# BSPD.net
KiCad netlist of a schematic drawn in EAGLE
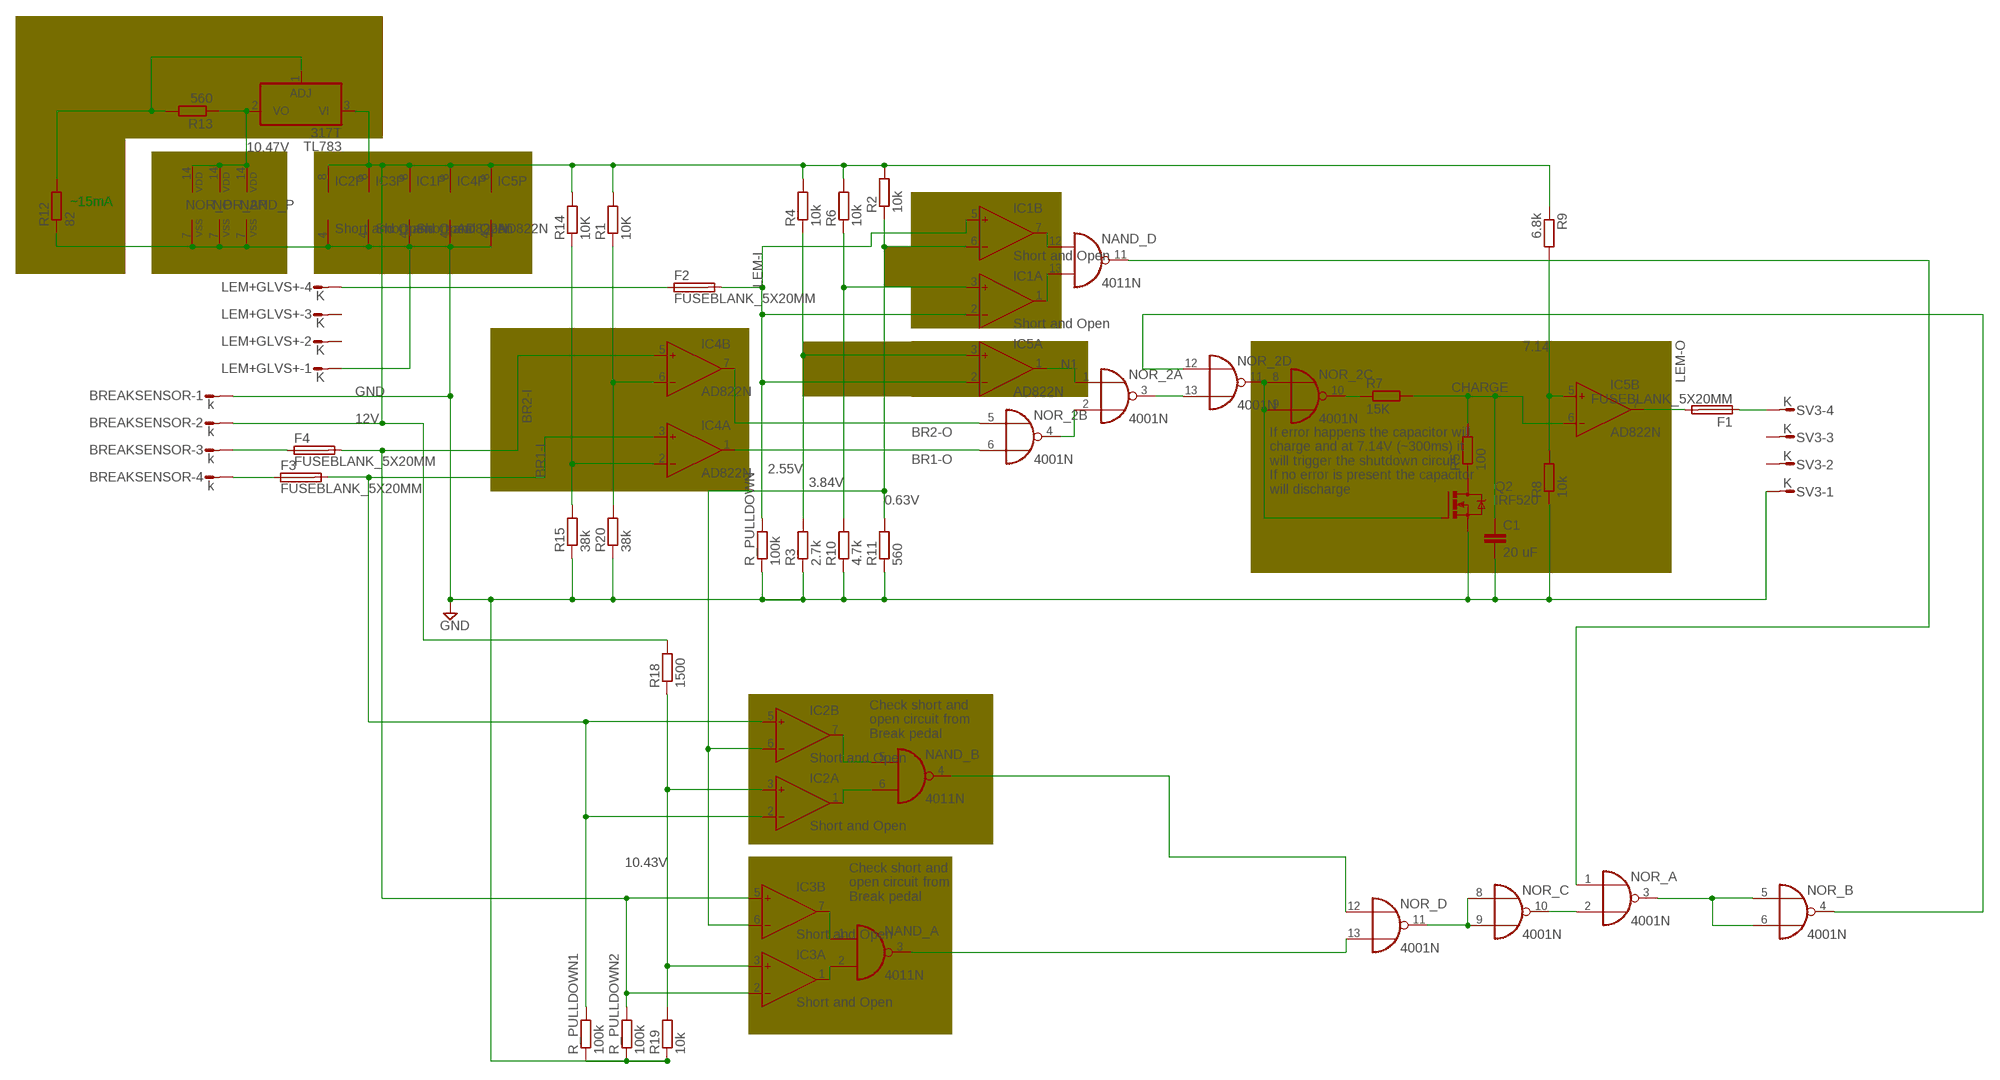
[diagram p0: schematic, sheet 1]

(export (version "E")
  (design (tool "Eeschema 10.0.6"))
  (components
    (comp (ref "BREAKSENSOR")
      (value "k")
      (footprint "eagle-import:L04P")
      (libsource (lib "eagle-import") (part "L04P"))
    )
    (comp (ref "C1")
      (value "20 uF")
      (footprint "eagle-import:C2.5-5")
      (libsource (lib "eagle-import") (part "C2.5/5"))
    )
    (comp (ref "F1")
      (value "FUSEBLANK_5X20MM")
      (footprint "eagle-import:FUSE_HOLDER_5X20MM")
      (libsource (lib "eagle-import") (part "FUSEBLANK_5X20MM"))
    )
    (comp (ref "F2")
      (value "FUSEBLANK_5X20MM")
      (footprint "eagle-import:FUSE_HOLDER_5X20MM")
      (libsource (lib "eagle-import") (part "FUSEBLANK_5X20MM"))
    )
    (comp (ref "F3")
      (value "FUSEBLANK_5X20MM")
      (footprint "eagle-import:FUSE_HOLDER_5X20MM")
      (libsource (lib "eagle-import") (part "FUSEBLANK_5X20MM"))
    )
    (comp (ref "F4")
      (value "FUSEBLANK_5X20MM")
      (footprint "eagle-import:FUSE_HOLDER_5X20MM")
      (libsource (lib "eagle-import") (part "FUSEBLANK_5X20MM"))
    )
    (comp (ref "IC1")
      (value "Short and Open")
      (footprint "eagle-import:DIL08")
      (libsource (lib "eagle-import") (part "AD822N"))
    )
    (comp (ref "IC2")
      (value "Short and Open")
      (footprint "eagle-import:DIL08")
      (libsource (lib "eagle-import") (part "AD822N"))
    )
    (comp (ref "IC3")
      (value "Short and Open")
      (footprint "eagle-import:DIL08")
      (libsource (lib "eagle-import") (part "AD822N"))
    )
    (comp (ref "IC4")
      (value "AD822N")
      (footprint "eagle-import:DIL08")
      (libsource (lib "eagle-import") (part "AD822N"))
    )
    (comp (ref "IC5")
      (value "AD822N")
      (footprint "eagle-import:DIL08")
      (libsource (lib "eagle-import") (part "AD822N"))
    )
    (comp (ref "LEM+GLVS+")
      (value "K")
      (footprint "eagle-import:L04P")
      (libsource (lib "eagle-import") (part "L04P"))
    )
    (comp (ref "NAND_")
      (value "4011N")
      (footprint "eagle-import:DIL14")
      (libsource (lib "eagle-import") (part "4011N"))
    )
    (comp (ref "NOR_")
      (value "4001N")
      (footprint "eagle-import:DIL14")
      (fields (field (name "SPICEPREFIX") "J"))
      (libsource (lib "eagle-import") (part "4001N"))
    )
    (comp (ref "NOR_2")
      (value "4001N")
      (footprint "eagle-import:DIL14")
      (fields (field (name "SPICEPREFIX") "J"))
      (libsource (lib "eagle-import") (part "4001N"))
    )
    (comp (ref "Q2")
      (value "IRF520")
      (footprint "eagle-import:TO220BV")
      (libsource (lib "eagle-import") (part "IRF520"))
    )
    (comp (ref "R1")
      (value "10K")
      (footprint "eagle-import:0204_7")
      (libsource (lib "eagle-import") (part "R-EU_0204/7"))
    )
    (comp (ref "R2")
      (value "10k")
      (footprint "eagle-import:0204_7")
      (libsource (lib "eagle-import") (part "R-EU_0204/7"))
    )
    (comp (ref "R3")
      (value "2.7k")
      (footprint "eagle-import:0204_7")
      (libsource (lib "eagle-import") (part "R-EU_0204/7"))
    )
    (comp (ref "R4")
      (value "10k")
      (footprint "eagle-import:0204_7")
      (libsource (lib "eagle-import") (part "R-EU_0204/7"))
    )
    (comp (ref "R5")
      (value "100")
      (footprint "eagle-import:0207_10")
      (libsource (lib "eagle-import") (part "resistor_348_R-EU_0207/10"))
    )
    (comp (ref "R6")
      (value "10k")
      (footprint "eagle-import:0204_7")
      (libsource (lib "eagle-import") (part "R-EU_0204/7"))
    )
    (comp (ref "R7")
      (value "15K")
      (footprint "eagle-import:0207_10")
      (libsource (lib "eagle-import") (part "resistor_348_R-EU_0207/10"))
    )
    (comp (ref "R8")
      (value "10k")
      (footprint "eagle-import:0204_7")
      (libsource (lib "eagle-import") (part "R-EU_0204/7"))
    )
    (comp (ref "R9")
      (value "6.8k")
      (footprint "eagle-import:0204_7")
      (libsource (lib "eagle-import") (part "R-EU_0204/7"))
    )
    (comp (ref "R10")
      (value "4.7k")
      (footprint "eagle-import:0204_7")
      (libsource (lib "eagle-import") (part "R-EU_0204/7"))
    )
    (comp (ref "R11")
      (value "560")
      (footprint "eagle-import:0204_7")
      (libsource (lib "eagle-import") (part "R-EU_0204/7"))
    )
    (comp (ref "R12")
      (value "82")
      (footprint "eagle-import:0204_7")
      (libsource (lib "eagle-import") (part "R-EU_0204/7"))
    )
    (comp (ref "R13")
      (value "560")
      (footprint "eagle-import:0204_7")
      (libsource (lib "eagle-import") (part "R-EU_0204/7"))
    )
    (comp (ref "R14")
      (value "10K")
      (footprint "eagle-import:0204_7")
      (libsource (lib "eagle-import") (part "R-EU_0204/7"))
    )
    (comp (ref "R15")
      (value "38k")
      (footprint "eagle-import:0207_10")
      (libsource (lib "eagle-import") (part "resistor_348_R-EU_0207/10"))
    )
    (comp (ref "R18")
      (value "1500")
      (footprint "eagle-import:0207_10")
      (libsource (lib "eagle-import") (part "resistor_348_R-EU_0207/10"))
    )
    (comp (ref "R19")
      (value "10k")
      (footprint "eagle-import:0207_10")
      (libsource (lib "eagle-import") (part "resistor_348_R-EU_0207/10"))
    )
    (comp (ref "R20")
      (value "38k")
      (footprint "eagle-import:0207_10")
      (libsource (lib "eagle-import") (part "resistor_348_R-EU_0207/10"))
    )
    (comp (ref "R_PULLDOWN")
      (value "100k")
      (footprint "eagle-import:0204_7")
      (libsource (lib "eagle-import") (part "R-EU_0204/7"))
    )
    (comp (ref "R_PULLDOWN1")
      (value "100k")
      (footprint "eagle-import:0204_7")
      (libsource (lib "eagle-import") (part "R-EU_0204/7"))
    )
    (comp (ref "R_PULLDOWN2")
      (value "100k")
      (footprint "eagle-import:0204_7")
      (libsource (lib "eagle-import") (part "R-EU_0204/7"))
    )
    (comp (ref "SV3")
      (value "K")
      (footprint "eagle-import:L04P")
      (libsource (lib "eagle-import") (part "L04P"))
    )
    (comp (ref "TL783")
      (value "317T")
      (footprint "eagle-import:TO220H")
      (libsource (lib "eagle-import") (part "317T"))
    )
  )
  (nets
    (net (code "1") (name "/0.63V") (class "Default")
      (node (ref "IC1") (pin "6") (pinfunction "IN-_6") (pintype "input"))
      (node (ref "IC2") (pin "6") (pinfunction "IN-_6") (pintype "input"))
      (node (ref "IC3") (pin "6") (pinfunction "IN-_6") (pintype "input"))
      (node (ref "R11") (pin "2") (pinfunction "2_2") (pintype "passive"))
      (node (ref "R2") (pin "1") (pinfunction "1_1") (pintype "passive"))
    )
    (net (code "2") (name "/2.55V") (class "Default")
      (node (ref "IC5") (pin "3") (pinfunction "IN+_3") (pintype "input"))
      (node (ref "R3") (pin "2") (pinfunction "2_2") (pintype "passive"))
      (node (ref "R4") (pin "1") (pinfunction "1_1") (pintype "passive"))
    )
    (net (code "3") (name "/3.84V") (class "Default")
      (node (ref "IC1") (pin "3") (pinfunction "IN+_3") (pintype "input"))
      (node (ref "R10") (pin "2") (pinfunction "2_2") (pintype "passive"))
      (node (ref "R6") (pin "1") (pinfunction "1_1") (pintype "passive"))
    )
    (net (code "4") (name "/7.14") (class "Default")
      (node (ref "IC5") (pin "5") (pinfunction "IN+_5") (pintype "input"))
      (node (ref "R8") (pin "2") (pinfunction "2_2") (pintype "passive"))
      (node (ref "R9") (pin "2") (pinfunction "2_2") (pintype "passive"))
    )
    (net (code "5") (name "/10.43V") (class "Default")
      (node (ref "IC2") (pin "3") (pinfunction "IN+_3") (pintype "input"))
      (node (ref "IC3") (pin "3") (pinfunction "IN+_3") (pintype "input"))
      (node (ref "R18") (pin "1") (pinfunction "1_1") (pintype "passive"))
      (node (ref "R19") (pin "2") (pinfunction "2_2") (pintype "passive"))
    )
    (net (code "6") (name "/10.47V") (class "Default")
      (node (ref "NAND_") (pin "14") (pinfunction "VDD_14") (pintype "power_in"))
      (node (ref "NOR_") (pin "14") (pinfunction "VDD_14") (pintype "power_in"))
      (node (ref "NOR_2") (pin "14") (pinfunction "VDD_14") (pintype "power_in"))
      (node (ref "R13") (pin "1") (pinfunction "1_1") (pintype "passive"))
      (node (ref "TL783") (pin "2") (pinfunction "VO_2") (pintype "passive"))
    )
    (net (code "7") (name "/12V") (class "Default")
      (node (ref "BREAKSENSOR") (pin "2") (pinfunction "S_2") (pintype "passive"))
      (node (ref "IC1") (pin "8") (pinfunction "V+_8") (pintype "power_in"))
      (node (ref "IC2") (pin "8") (pinfunction "V+_8") (pintype "power_in"))
      (node (ref "IC3") (pin "8") (pinfunction "V+_8") (pintype "power_in"))
      (node (ref "IC4") (pin "8") (pinfunction "V+_8") (pintype "power_in"))
      (node (ref "IC5") (pin "8") (pinfunction "V+_8") (pintype "power_in"))
      (node (ref "R1") (pin "2") (pinfunction "2_2") (pintype "passive"))
      (node (ref "R14") (pin "2") (pinfunction "2_2") (pintype "passive"))
      (node (ref "R18") (pin "2") (pinfunction "2_2") (pintype "passive"))
      (node (ref "R2") (pin "2") (pinfunction "2_2") (pintype "passive"))
      (node (ref "R4") (pin "2") (pinfunction "2_2") (pintype "passive"))
      (node (ref "R6") (pin "2") (pinfunction "2_2") (pintype "passive"))
      (node (ref "R9") (pin "1") (pinfunction "1_1") (pintype "passive"))
      (node (ref "TL783") (pin "3") (pinfunction "VI_3") (pintype "input"))
    )
    (net (code "8") (name "/BR1-I") (class "Default")
      (node (ref "F3") (pin "2") (pinfunction "2_2") (pintype "passive"))
      (node (ref "IC2") (pin "2") (pinfunction "IN-_2") (pintype "input"))
      (node (ref "IC2") (pin "5") (pinfunction "IN+_5") (pintype "input"))
      (node (ref "IC4") (pin "3") (pinfunction "IN+_3") (pintype "input"))
      (node (ref "R_PULLDOWN1") (pin "2") (pinfunction "2_2") (pintype "passive"))
    )
    (net (code "9") (name "/BR1-O") (class "Default")
      (node (ref "IC4") (pin "1") (pinfunction "OUT_1") (pintype "output"))
      (node (ref "NOR_2") (pin "6") (pinfunction "I1_6") (pintype "input"))
    )
    (net (code "10") (name "/BR2-I") (class "Default")
      (node (ref "F4") (pin "2") (pinfunction "2_2") (pintype "passive"))
      (node (ref "IC3") (pin "2") (pinfunction "IN-_2") (pintype "input"))
      (node (ref "IC3") (pin "5") (pinfunction "IN+_5") (pintype "input"))
      (node (ref "IC4") (pin "5") (pinfunction "IN+_5") (pintype "input"))
      (node (ref "R_PULLDOWN2") (pin "2") (pinfunction "2_2") (pintype "passive"))
    )
    (net (code "11") (name "/BR2-O") (class "Default")
      (node (ref "IC4") (pin "7") (pinfunction "OUT_7") (pintype "output"))
      (node (ref "NOR_2") (pin "5") (pinfunction "I0_5") (pintype "input"))
    )
    (net (code "12") (name "/CHARGE") (class "Default")
      (node (ref "C1") (pin "1") (pinfunction "1_1") (pintype "passive"))
      (node (ref "IC5") (pin "6") (pinfunction "IN-_6") (pintype "input"))
      (node (ref "R5") (pin "2") (pinfunction "2_2") (pintype "passive"))
      (node (ref "R7") (pin "2") (pinfunction "2_2") (pintype "passive"))
    )
    (net (code "13") (name "/LEM-I") (class "Default")
      (node (ref "F2") (pin "2") (pinfunction "2_2") (pintype "passive"))
      (node (ref "IC1") (pin "2") (pinfunction "IN-_2") (pintype "input"))
      (node (ref "IC1") (pin "5") (pinfunction "IN+_5") (pintype "input"))
      (node (ref "IC5") (pin "2") (pinfunction "IN-_2") (pintype "input"))
      (node (ref "R_PULLDOWN") (pin "2") (pinfunction "2_2") (pintype "passive"))
    )
    (net (code "14") (name "/LEM-O") (class "Default")
      (node (ref "F1") (pin "2") (pinfunction "2_2") (pintype "passive"))
      (node (ref "IC5") (pin "7") (pinfunction "OUT_7") (pintype "output"))
    )
    (net (code "15") (name "/N1") (class "Default")
      (node (ref "IC5") (pin "1") (pinfunction "OUT_1") (pintype "output"))
      (node (ref "NOR_2") (pin "1") (pinfunction "I0_1") (pintype "input"))
    )
    (net (code "16") (name "GND") (class "Default")
      (node (ref "BREAKSENSOR") (pin "1") (pinfunction "S_1") (pintype "passive"))
      (node (ref "C1") (pin "2") (pinfunction "2_2") (pintype "passive"))
      (node (ref "IC1") (pin "4") (pinfunction "V-_4") (pintype "power_in"))
      (node (ref "IC2") (pin "4") (pinfunction "V-_4") (pintype "power_in"))
      (node (ref "IC3") (pin "4") (pinfunction "V-_4") (pintype "power_in"))
      (node (ref "IC4") (pin "4") (pinfunction "V-_4") (pintype "power_in"))
      (node (ref "IC5") (pin "4") (pinfunction "V-_4") (pintype "power_in"))
      (node (ref "LEM+GLVS+") (pin "1") (pinfunction "S_1") (pintype "passive"))
      (node (ref "NAND_") (pin "7") (pinfunction "VSS_7") (pintype "power_in"))
      (node (ref "NOR_") (pin "7") (pinfunction "VSS_7") (pintype "power_in"))
      (node (ref "NOR_2") (pin "7") (pinfunction "VSS_7") (pintype "power_in"))
      (node (ref "Q2") (pin "S") (pinfunction "S_S") (pintype "passive"))
      (node (ref "R10") (pin "1") (pinfunction "1_1") (pintype "passive"))
      (node (ref "R11") (pin "1") (pinfunction "1_1") (pintype "passive"))
      (node (ref "R12") (pin "1") (pinfunction "1_1") (pintype "passive"))
      (node (ref "R15") (pin "1") (pinfunction "1_1") (pintype "passive"))
      (node (ref "R19") (pin "1") (pinfunction "1_1") (pintype "passive"))
      (node (ref "R20") (pin "1") (pinfunction "1_1") (pintype "passive"))
      (node (ref "R3") (pin "1") (pinfunction "1_1") (pintype "passive"))
      (node (ref "R8") (pin "1") (pinfunction "1_1") (pintype "passive"))
      (node (ref "R_PULLDOWN") (pin "1") (pinfunction "1_1") (pintype "passive"))
      (node (ref "R_PULLDOWN1") (pin "1") (pinfunction "1_1") (pintype "passive"))
      (node (ref "R_PULLDOWN2") (pin "1") (pinfunction "1_1") (pintype "passive"))
      (node (ref "SV3") (pin "1") (pinfunction "S_1") (pintype "passive"))
    )
    (net (code "17") (name "Net-(BREAKSENSORC-S)") (class "Default")
      (node (ref "BREAKSENSOR") (pin "3") (pinfunction "S_3") (pintype "passive"))
      (node (ref "F4") (pin "1") (pinfunction "1_1") (pintype "passive"))
    )
    (net (code "18") (name "Net-(BREAKSENSORD-S)") (class "Default")
      (node (ref "BREAKSENSOR") (pin "4") (pinfunction "S_4") (pintype "passive"))
      (node (ref "F3") (pin "1") (pinfunction "1_1") (pintype "passive"))
    )
    (net (code "19") (name "Net-(IC1A-OUT)") (class "Default")
      (node (ref "IC1") (pin "1") (pinfunction "OUT_1") (pintype "output"))
      (node (ref "NAND_") (pin "13") (pinfunction "I1_13") (pintype "input"))
    )
    (net (code "20") (name "Net-(IC1B-OUT)") (class "Default")
      (node (ref "IC1") (pin "7") (pinfunction "OUT_7") (pintype "output"))
      (node (ref "NAND_") (pin "12") (pinfunction "I0_12") (pintype "input"))
    )
    (net (code "21") (name "Net-(IC2A-OUT)") (class "Default")
      (node (ref "IC2") (pin "1") (pinfunction "OUT_1") (pintype "output"))
      (node (ref "NAND_") (pin "6") (pinfunction "I1_6") (pintype "input"))
    )
    (net (code "22") (name "Net-(IC2B-OUT)") (class "Default")
      (node (ref "IC2") (pin "7") (pinfunction "OUT_7") (pintype "output"))
      (node (ref "NAND_") (pin "5") (pinfunction "I0_5") (pintype "input"))
    )
    (net (code "23") (name "Net-(IC3A-OUT)") (class "Default")
      (node (ref "IC3") (pin "1") (pinfunction "OUT_1") (pintype "output"))
      (node (ref "NAND_") (pin "2") (pinfunction "I1_2") (pintype "input"))
    )
    (net (code "24") (name "Net-(IC3B-OUT)") (class "Default")
      (node (ref "IC3") (pin "7") (pinfunction "OUT_7") (pintype "output"))
      (node (ref "NAND_") (pin "1") (pinfunction "I0_1") (pintype "input"))
    )
    (net (code "25") (name "Net-(IC4A-IN-)") (class "Default")
      (node (ref "IC4") (pin "2") (pinfunction "IN-_2") (pintype "input"))
      (node (ref "R14") (pin "1") (pinfunction "1_1") (pintype "passive"))
      (node (ref "R15") (pin "2") (pinfunction "2_2") (pintype "passive"))
    )
    (net (code "26") (name "Net-(IC4B-IN-)") (class "Default")
      (node (ref "IC4") (pin "6") (pinfunction "IN-_6") (pintype "input"))
      (node (ref "R1") (pin "1") (pinfunction "1_1") (pintype "passive"))
      (node (ref "R20") (pin "2") (pinfunction "2_2") (pintype "passive"))
    )
    (net (code "27") (name "Net-(LEM+GLVS+D-S)") (class "Default")
      (node (ref "F2") (pin "1") (pinfunction "1_1") (pintype "passive"))
      (node (ref "LEM+GLVS+") (pin "4") (pinfunction "S_4") (pintype "passive"))
    )
    (net (code "28") (name "Net-(NAND_A-O)") (class "Default")
      (node (ref "NAND_") (pin "3") (pinfunction "O_3") (pintype "output"))
      (node (ref "NOR_") (pin "13") (pinfunction "I1_13") (pintype "input"))
    )
    (net (code "29") (name "Net-(NAND_B-O)") (class "Default")
      (node (ref "NAND_") (pin "4") (pinfunction "O_4") (pintype "output"))
      (node (ref "NOR_") (pin "12") (pinfunction "I0_12") (pintype "input"))
    )
    (net (code "30") (name "Net-(NAND_D-O)") (class "Default")
      (node (ref "NAND_") (pin "11") (pinfunction "O_11") (pintype "output"))
      (node (ref "NOR_") (pin "1") (pinfunction "I0_1") (pintype "input"))
    )
    (net (code "31") (name "Net-(NOR_2A-I1)") (class "Default")
      (node (ref "NOR_2") (pin "2") (pinfunction "I1_2") (pintype "input"))
      (node (ref "NOR_2") (pin "4") (pinfunction "O_4") (pintype "output"))
    )
    (net (code "32") (name "Net-(NOR_2A-O)") (class "Default")
      (node (ref "NOR_2") (pin "13") (pinfunction "I1_13") (pintype "input"))
      (node (ref "NOR_2") (pin "3") (pinfunction "O_3") (pintype "output"))
    )
    (net (code "33") (name "Net-(NOR_2C-I0)") (class "Default")
      (node (ref "NOR_2") (pin "11") (pinfunction "O_11") (pintype "output"))
      (node (ref "NOR_2") (pin "8") (pinfunction "I0_8") (pintype "input"))
      (node (ref "NOR_2") (pin "9") (pinfunction "I1_9") (pintype "input"))
      (node (ref "Q2") (pin "G") (pinfunction "G_G") (pintype "passive"))
    )
    (net (code "34") (name "Net-(NOR_2C-O)") (class "Default")
      (node (ref "NOR_2") (pin "10") (pinfunction "O_10") (pintype "output"))
      (node (ref "R7") (pin "1") (pinfunction "1_1") (pintype "passive"))
    )
    (net (code "35") (name "Net-(NOR_2D-I0)") (class "Default")
      (node (ref "NOR_") (pin "4") (pinfunction "O_4") (pintype "output"))
      (node (ref "NOR_2") (pin "12") (pinfunction "I0_12") (pintype "input"))
    )
    (net (code "36") (name "Net-(NOR_A-I1)") (class "Default")
      (node (ref "NOR_") (pin "10") (pinfunction "O_10") (pintype "output"))
      (node (ref "NOR_") (pin "2") (pinfunction "I1_2") (pintype "input"))
    )
    (net (code "37") (name "Net-(NOR_A-O)") (class "Default")
      (node (ref "NOR_") (pin "3") (pinfunction "O_3") (pintype "output"))
      (node (ref "NOR_") (pin "5") (pinfunction "I0_5") (pintype "input"))
      (node (ref "NOR_") (pin "6") (pinfunction "I1_6") (pintype "input"))
    )
    (net (code "38") (name "Net-(NOR_C-I0)") (class "Default")
      (node (ref "NOR_") (pin "11") (pinfunction "O_11") (pintype "output"))
      (node (ref "NOR_") (pin "8") (pinfunction "I0_8") (pintype "input"))
      (node (ref "NOR_") (pin "9") (pinfunction "I1_9") (pintype "input"))
    )
    (net (code "39") (name "Net-(Q2-PadD)") (class "Default")
      (node (ref "Q2") (pin "D") (pinfunction "D_D") (pintype "passive"))
      (node (ref "R5") (pin "1") (pinfunction "1_1") (pintype "passive"))
    )
    (net (code "40") (name "Net-(SV3D-S)") (class "Default")
      (node (ref "F1") (pin "1") (pinfunction "1_1") (pintype "passive"))
      (node (ref "SV3") (pin "4") (pinfunction "S_4") (pintype "passive"))
    )
    (net (code "41") (name "Net-(TL783-ADJ)") (class "Default")
      (node (ref "R12") (pin "2") (pinfunction "2_2") (pintype "passive"))
      (node (ref "R13") (pin "2") (pinfunction "2_2") (pintype "passive"))
      (node (ref "TL783") (pin "1") (pinfunction "ADJ_1") (pintype "input"))
    )
    (net (code "42") (name "unconnected-(LEM+GLVS+B-S-Pad2)") (class "Default")
      (node (ref "LEM+GLVS+") (pin "2") (pinfunction "S_2") (pintype "passive"))
    )
    (net (code "43") (name "unconnected-(LEM+GLVS+C-S-Pad3)") (class "Default")
      (node (ref "LEM+GLVS+") (pin "3") (pinfunction "S_3") (pintype "passive"))
    )
    (net (code "44") (name "unconnected-(SV3B-S-Pad2)") (class "Default")
      (node (ref "SV3") (pin "2") (pinfunction "S_2") (pintype "passive"))
    )
    (net (code "45") (name "unconnected-(SV3C-S-Pad3)") (class "Default")
      (node (ref "SV3") (pin "3") (pinfunction "S_3") (pintype "passive"))
    )
  )
)
